# RS232.net
KiCad netlist of a schematic drawn in Altium Designer
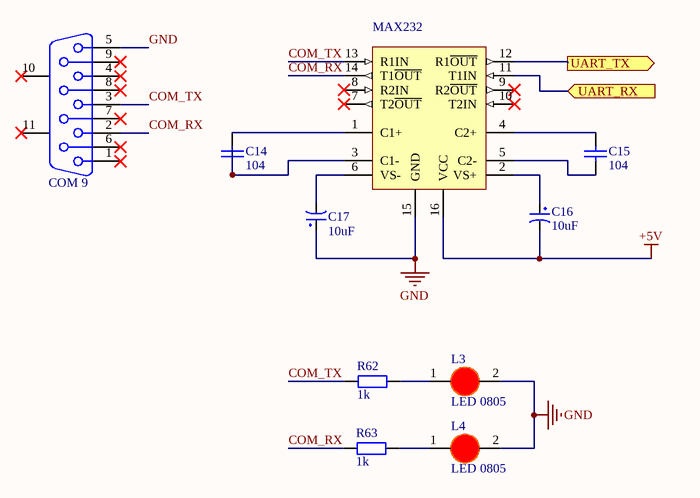
[diagram p0: RS232.SchDoc]

(export (version "E")
  (design (tool "Eeschema 10.0.6"))
  (components
    (comp (ref "C14")
      (value "104")
      (footprint "tu 0805")
      (description "Dán")
      (libsource (lib "Altium_Lib_by_KhueNguyenCreator") (part "Tu 0805 104 50V 10%"))
    )
    (comp (ref "C15")
      (value "104")
      (footprint "tu 0805")
      (description "Dán")
      (libsource (lib "Altium_Lib_by_KhueNguyenCreator") (part "Tu 0805 104 50V 10%"))
    )
    (comp (ref "C16")
      (value "10uF")
      (footprint "tu hoa 4mm")
      (description "Cắm")
      (libsource (lib "Altium_Lib_by_KhueNguyenCreator") (part "Tu Hoa 10uF 25V 4x7"))
    )
    (comp (ref "C17")
      (value "10uF")
      (footprint "tu hoa 4mm")
      (description "Cắm")
      (libsource (lib "Altium_Lib_by_KhueNguyenCreator") (part "Tu Hoa 10uF 25V 4x7"))
    )
    (comp (ref "COM1")
      (value "COM 9")
      (footprint "DSB 9-F")
      (fields (field (name "PUBLISHER") "Altium Limited"))
      (libsource (lib "My library altium") (part "COM 9 DSB"))
    )
    (comp (ref "IC4")
      (value "MAX232")
      (footprint "MAX-232")
      (description "Dual EIA-232 Driver/Receiver")
      (libsource (lib "My library altium") (part "MAX232"))
    )
    (comp (ref "L3")
      (value "LED 0805")
      (footprint "LED-0805-Red")
      (description "Dán")
      (libsource (lib "Altium_Lib_by_KhueNguyenCreator") (part "LED 0805 Do"))
    )
    (comp (ref "L4")
      (value "LED 0805")
      (footprint "LED-0805-Red")
      (description "Dán")
      (libsource (lib "Altium_Lib_by_KhueNguyenCreator") (part "LED 0805 Do"))
    )
    (comp (ref "R62")
      (value "1k")
      (footprint "tro smd 0805")
      (description "Dán")
      (libsource (lib "Altium_Lib_by_KhueNguyenCreator") (part "Tro 0805 1% 1k"))
    )
    (comp (ref "R63")
      (value "1k")
      (footprint "tro smd 0805")
      (description "Dán")
      (libsource (lib "Altium_Lib_by_KhueNguyenCreator") (part "Tro 0805 1% 1k"))
    )
  )
  (nets
    (net (code "1") (name "+5V") (class "Default")
      (node (ref "C16") (pin "2") (pinfunction "2_2") (pintype "passive"))
      (node (ref "IC4") (pin "16") (pinfunction "VCC_16") (pintype "power_in"))
    )
    (net (code "2") (name "/COM_RX") (class "Default")
      (node (ref "COM1") (pin "2") (pinfunction "2_2") (pintype "passive"))
      (node (ref "IC4") (pin "14") (pinfunction "T1~{OUT}_14") (pintype "output"))
      (node (ref "R63") (pin "1") (pinfunction "1_1") (pintype "passive"))
    )
    (net (code "3") (name "/COM_TX") (class "Default")
      (node (ref "COM1") (pin "3") (pinfunction "3_3") (pintype "passive"))
      (node (ref "IC4") (pin "13") (pinfunction "R1IN_13") (pintype "input"))
      (node (ref "R62") (pin "1") (pinfunction "1_1") (pintype "passive"))
    )
    (net (code "4") (name "/UART_RX") (class "Default")
      (node (ref "IC4") (pin "11") (pinfunction "T1IN_11") (pintype "input"))
    )
    (net (code "5") (name "/UART_TX") (class "Default")
      (node (ref "IC4") (pin "12") (pinfunction "R1~{OUT}_12") (pintype "output"))
    )
    (net (code "6") (name "GND") (class "Default")
      (node (ref "C17") (pin "1") (pinfunction "1_1") (pintype "passive"))
      (node (ref "COM1") (pin "5") (pinfunction "5_5") (pintype "passive"))
      (node (ref "IC4") (pin "15") (pinfunction "GND_15") (pintype "power_in"))
      (node (ref "L3") (pin "2") (pinfunction "K_2") (pintype "passive"))
      (node (ref "L4") (pin "2") (pinfunction "K_2") (pintype "passive"))
    )
    (net (code "7") (name "Net-(IC4-C1+)") (class "Default")
      (node (ref "C14") (pin "1") (pinfunction "1_1") (pintype "passive"))
      (node (ref "IC4") (pin "1") (pinfunction "C1+_1") (pintype "passive"))
    )
    (net (code "8") (name "Net-(IC4-C1-)") (class "Default")
      (node (ref "C14") (pin "2") (pinfunction "2_2") (pintype "passive"))
      (node (ref "IC4") (pin "3") (pinfunction "C1-_3") (pintype "passive"))
    )
    (net (code "9") (name "Net-(IC4-C2+)") (class "Default")
      (node (ref "C15") (pin "1") (pinfunction "1_1") (pintype "passive"))
      (node (ref "IC4") (pin "4") (pinfunction "C2+_4") (pintype "passive"))
    )
    (net (code "10") (name "Net-(IC4-C2-)") (class "Default")
      (node (ref "C15") (pin "2") (pinfunction "2_2") (pintype "passive"))
      (node (ref "IC4") (pin "5") (pinfunction "C2-_5") (pintype "passive"))
    )
    (net (code "11") (name "Net-(IC4-VS+)") (class "Default")
      (node (ref "C16") (pin "1") (pinfunction "1_1") (pintype "passive"))
      (node (ref "IC4") (pin "2") (pinfunction "VS+_2") (pintype "power_in"))
    )
    (net (code "12") (name "Net-(IC4-VS-)") (class "Default")
      (node (ref "C17") (pin "2") (pinfunction "2_2") (pintype "passive"))
      (node (ref "IC4") (pin "6") (pinfunction "VS-_6") (pintype "power_in"))
    )
    (net (code "13") (name "Net-(L3-A)") (class "Default")
      (node (ref "L3") (pin "1") (pinfunction "A_1") (pintype "passive"))
      (node (ref "R62") (pin "2") (pinfunction "2_2") (pintype "passive"))
    )
    (net (code "14") (name "Net-(L4-A)") (class "Default")
      (node (ref "L4") (pin "1") (pinfunction "A_1") (pintype "passive"))
      (node (ref "R63") (pin "2") (pinfunction "2_2") (pintype "passive"))
    )
    (net (code "15") (name "unconnected-(COM1-MH1-Pad10)") (class "Default")
      (node (ref "COM1") (pin "10") (pinfunction "MH1_10") (pintype "passive+no_connect"))
    )
    (net (code "16") (name "unconnected-(COM1-MH2-Pad11)") (class "Default")
      (node (ref "COM1") (pin "11") (pinfunction "MH2_11") (pintype "passive+no_connect"))
    )
    (net (code "17") (name "unconnected-(COM1-Pad1)") (class "Default")
      (node (ref "COM1") (pin "1") (pinfunction "1_1") (pintype "passive+no_connect"))
    )
    (net (code "18") (name "unconnected-(COM1-Pad4)") (class "Default")
      (node (ref "COM1") (pin "4") (pinfunction "4_4") (pintype "passive+no_connect"))
    )
    (net (code "19") (name "unconnected-(COM1-Pad6)") (class "Default")
      (node (ref "COM1") (pin "6") (pinfunction "6_6") (pintype "passive+no_connect"))
    )
    (net (code "20") (name "unconnected-(COM1-Pad7)") (class "Default")
      (node (ref "COM1") (pin "7") (pinfunction "7_7") (pintype "passive+no_connect"))
    )
    (net (code "21") (name "unconnected-(COM1-Pad8)") (class "Default")
      (node (ref "COM1") (pin "8") (pinfunction "8_8") (pintype "passive+no_connect"))
    )
    (net (code "22") (name "unconnected-(COM1-Pad9)") (class "Default")
      (node (ref "COM1") (pin "9") (pinfunction "9_9") (pintype "passive+no_connect"))
    )
    (net (code "23") (name "unconnected-(IC4-R2IN-Pad8)") (class "Default")
      (node (ref "IC4") (pin "8") (pinfunction "R2IN_8") (pintype "input+no_connect"))
    )
    (net (code "24") (name "unconnected-(IC4-R2~{OUT}-Pad9)") (class "Default")
      (node (ref "IC4") (pin "9") (pinfunction "R2~{OUT}_9") (pintype "output+no_connect"))
    )
    (net (code "25") (name "unconnected-(IC4-T2IN-Pad10)") (class "Default")
      (node (ref "IC4") (pin "10") (pinfunction "T2IN_10") (pintype "input+no_connect"))
    )
    (net (code "26") (name "unconnected-(IC4-T2~{OUT}-Pad7)") (class "Default")
      (node (ref "IC4") (pin "7") (pinfunction "T2~{OUT}_7") (pintype "output+no_connect"))
    )
  )
)
